# LTC6268-diff-iso.net
KiCad netlist of a schematic drawn in Altium Designer
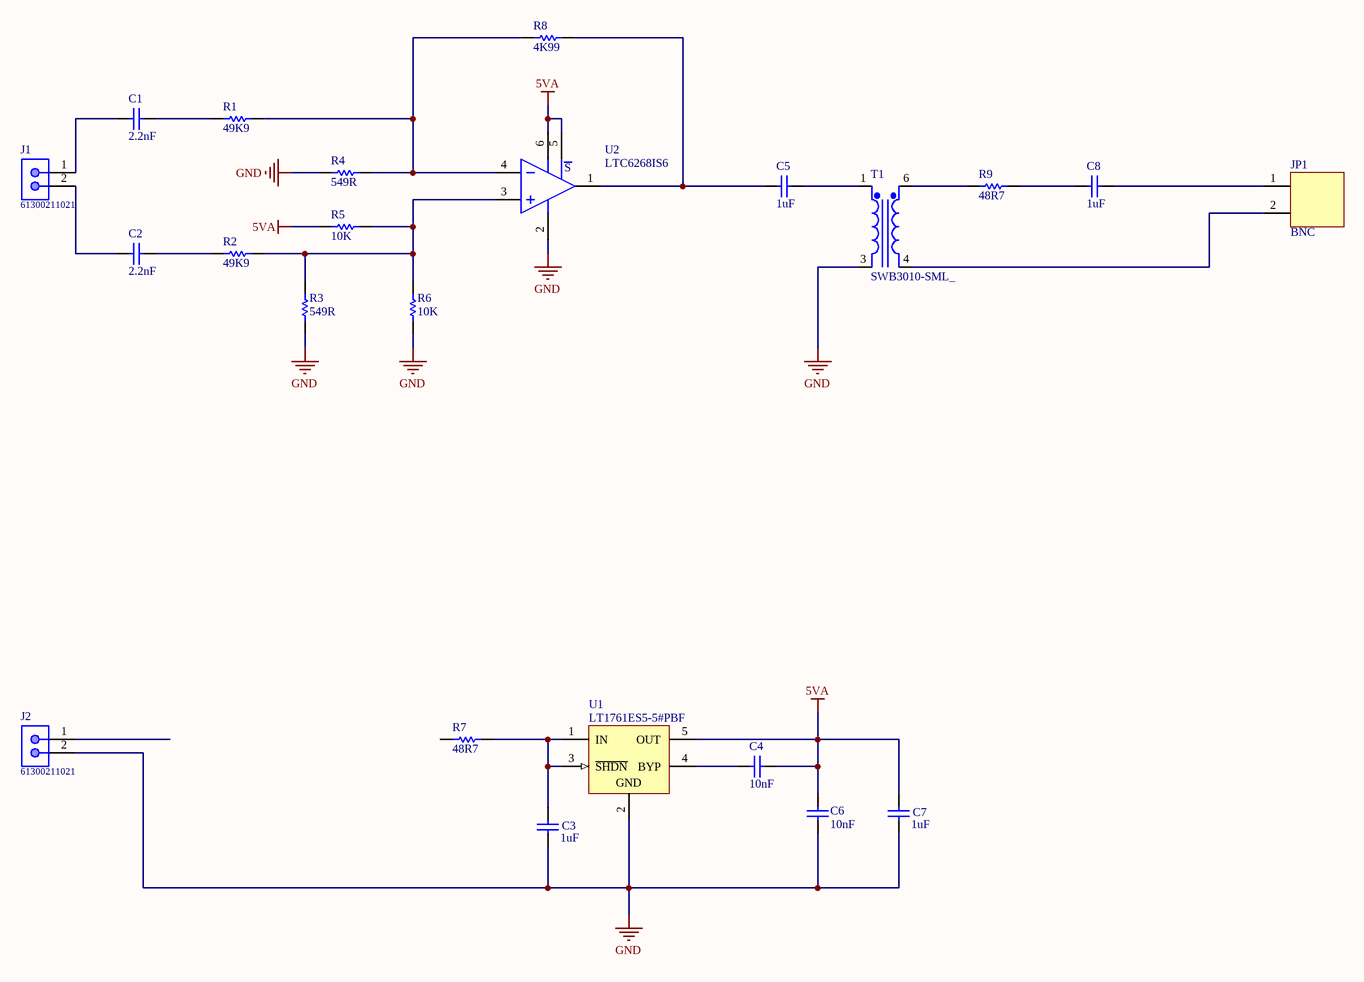
[diagram p0: LTC6268-diff-iso.SchDoc]

(export (version "E")
  (design (tool "Eeschema 10.0.6"))
  (components
    (comp (ref "C1")
      (value "2.2nF")
      (footprint "CAPC1210(3225)170_L")
      (description "CAP 2.2nF 630V ±5% 1210 (3225 Metric) Thickness 1.7mm SMD")
      (fields (field (name "TOLERANCE") "Â±5%") (field (name "MPN") "C1210C222JDGACTU"))
      (libsource (lib "Altium Content Vault") (part "CAP"))
    )
    (comp (ref "C2")
      (value "2.2nF")
      (footprint "CAPC1210(3225)170_L")
      (description "CAP 2.2nF 630V ±5% 1210 (3225 Metric) Thickness 1.7mm SMD")
      (fields (field (name "TOLERANCE") "Â±5%") (field (name "MPN") "C1210C222JDGACTU"))
      (libsource (lib "Altium Content Vault") (part "CAP"))
    )
    (comp (ref "C3")
      (value "1uF")
      (footprint "CAPC0805(2012)145_L")
      (description "CAP 1uF 16V ±10% 0805 (2012 Metric) Thickness 1.45mm SMD")
      (fields (field (name "TOLERANCE") "Â±10%") (field (name "Comment") "CAP 1uF 16V 0805(2012)"))
      (libsource (lib "Altium Content Vault") (part "CAP"))
    )
    (comp (ref "C4")
      (value "10nF")
      (footprint "CAPC0402(1005)33_N")
      (description "CAP 10nF 16V ±10% 0402 (1005 Metric) Thickness 0.33mm SMD")
      (fields (field (name "TOLERANCE") "Â±10%") (field (name "Comment") "CAP 10nF 16V 0402(1005)"))
      (libsource (lib "Altium Content Vault") (part "CAP"))
    )
    (comp (ref "C5")
      (value "1uF")
      (footprint "CAPC1210(3225)135_L")
      (description "CAP FILM 1UF 20% 16VDC 1210")
      (fields (field (name "MPN") "FCA1210C105M-G2") (field (name "VOLTAGE") "16V"))
      (libsource (lib "altium-import") (part "root_0_CAP_1210_1UF16V_FCA_"))
    )
    (comp (ref "C6")
      (value "10nF")
      (footprint "CAPC0402(1005)33_N")
      (description "CAP 10nF 16V ±10% 0402 (1005 Metric) Thickness 0.33mm SMD")
      (fields (field (name "TOLERANCE") "Â±10%") (field (name "Comment") "CAP 10nF 16V 0402(1005)"))
      (libsource (lib "Altium Content Vault") (part "CAP"))
    )
    (comp (ref "C7")
      (value "1uF")
      (footprint "CAPC0805(2012)145_L")
      (description "CAP 1uF 16V ±10% 0805 (2012 Metric) Thickness 1.45mm SMD")
      (fields (field (name "TOLERANCE") "Â±10%") (field (name "Comment") "CAP 1uF 16V 0805(2012)"))
      (libsource (lib "Altium Content Vault") (part "CAP"))
    )
    (comp (ref "C8")
      (value "1uF")
      (footprint "CAPC1210(3225)135_L")
      (description "CAP FILM 1UF 20% 16VDC 1210")
      (fields (field (name "MPN") "FCA1210C105M-G2") (field (name "VOLTAGE") "16V"))
      (libsource (lib "altium-import") (part "root_0_CAP_1210_1UF16V_FCA_"))
    )
    (comp (ref "J1")
      (value "61300211021")
      (footprint "61300211021")
      (description "THT Angled Pin Header WR-PHD, Pitch 2.54 mm, Single Row, 2 pins")
      (fields (field (name "PUBLISHER") "Wurth Elektronik"))
      (libsource (lib "altium-import") (part "root_0_mirrored_61300211021_"))
    )
    (comp (ref "J2")
      (value "61300211021")
      (footprint "61300211021")
      (description "THT Angled Pin Header WR-PHD, Pitch 2.54 mm, Single Row, 2 pins")
      (fields (field (name "PUBLISHER") "Wurth Elektronik"))
      (libsource (lib "altium-import") (part "root_0_mirrored_61300211021_"))
    )
    (comp (ref "JP1")
      (value "BNC")
      (footprint "CONN-BNC-1-1337542-0")
      (description "BNC Connector Jack, Female Socket 50 Ohm Panel Mount, Through Hole, Right Angle Solder")
      (fields (field (name "MPN") "1-1337542-0"))
      (libsource (lib "altium-import") (part "root_0_CONN-BNC-1-1337542-0_"))
    )
    (comp (ref "R1")
      (value "49K9")
      (footprint "RESC0402(1005)_N")
      (description "49K9 0.063W 1% 0402 (1005 Metric)  SMD")
      (fields (field (name "POWER") "0.063 W") (field (name "TOLERANCE") "1 %"))
      (libsource (lib "Altium Content Vault") (part "RES"))
    )
    (comp (ref "R2")
      (value "49K9")
      (footprint "RESC0402(1005)_N")
      (description "49K9 0.063W 1% 0402 (1005 Metric)  SMD")
      (fields (field (name "POWER") "0.063 W") (field (name "TOLERANCE") "1 %"))
      (libsource (lib "Altium Content Vault") (part "RES"))
    )
    (comp (ref "R3")
      (value "549R")
      (footprint "RESC0402(1005)_N")
      (description "549R 0.063W 1% 0402 (1005 Metric)  SMD")
      (fields (field (name "TOLERANCE") "1 %") (field (name "POWER") "0.063 W"))
      (libsource (lib "Altium Content Vault") (part "RES"))
    )
    (comp (ref "R4")
      (value "549R")
      (footprint "RESC0402(1005)_N")
      (description "549R 0.063W 1% 0402 (1005 Metric)  SMD")
      (fields (field (name "TOLERANCE") "1 %") (field (name "POWER") "0.063 W"))
      (libsource (lib "Altium Content Vault") (part "RES"))
    )
    (comp (ref "R5")
      (value "10K")
      (footprint "RESC0402(1005)_N")
      (description "10K 0.063W 1% 0402 (1005 Metric)  SMD")
      (fields (field (name "TOLERANCE") "1 %") (field (name "POWER") "0.063 W"))
      (libsource (lib "Altium Content Vault") (part "RES"))
    )
    (comp (ref "R6")
      (value "10K")
      (footprint "RESC0402(1005)_N")
      (description "10K 0.063W 1% 0402 (1005 Metric)  SMD")
      (fields (field (name "TOLERANCE") "1 %") (field (name "POWER") "0.063 W"))
      (libsource (lib "Altium Content Vault") (part "RES"))
    )
    (comp (ref "R7")
      (value "48R7")
      (footprint "RESC0402(1005)_N")
      (description "48R7 0.063W 1% 0402 (1005 Metric)  SMD")
      (fields (field (name "TOLERANCE") "1 %") (field (name "POWER") "0.063 W"))
      (libsource (lib "Altium Content Vault") (part "RES"))
    )
    (comp (ref "R8")
      (value "4K99")
      (footprint "RESC0402(1005)_N")
      (description "4K99 0.063W 1% 0402 (1005 Metric)  SMD")
      (fields (field (name "TOLERANCE") "1 %") (field (name "POWER") "0.063 W"))
      (libsource (lib "Altium Content Vault") (part "RES"))
    )
    (comp (ref "R9")
      (value "48R7")
      (footprint "RESC0402(1005)_N")
      (description "48R7 0.063W 1% 0402 (1005 Metric)  SMD")
      (fields (field (name "TOLERANCE") "1 %") (field (name "POWER") "0.063 W"))
      (libsource (lib "Altium Content Vault") (part "RES"))
    )
    (comp (ref "T1")
      (value "SWB3010-SML_")
      (footprint "Coilcraft-SWB")
      (description "Wideband RF Transformers – SWB")
      (libsource (lib "wemo") (part "TRANS-SWB3010-SML_"))
    )
    (comp (ref "U1")
      (value "LT1761ES5-5#PBF")
      (footprint "LT-S5-5-TSOT-23_M")
      (fields (field (name "MANUFACTURER") "Linear Technology"))
      (libsource (lib "Altium Content Vault") (part "LT-LTXXXXX-S5-5"))
    )
    (comp (ref "U2")
      (value "LTC6268IS6")
      (footprint "LT-S6-6-TSOT-23_L")
      (description "IC OPAMP 500MHZ SGL FET TSOT23-6")
      (fields (field (name "MPN") "LTC6268IS6#TRMPBF"))
      (libsource (lib "altium-import") (part "root_0_IC-LINEAR-LTC6268IS6#TRMPBF_"))
    )
  )
  (nets
    (net (code "1") (name "5VA") (class "Default")
      (node (ref "C4") (pin "1") (pinfunction "1_1") (pintype "passive"))
      (node (ref "C6") (pin "1") (pinfunction "1_1") (pintype "passive"))
      (node (ref "C7") (pin "2") (pinfunction "2_2") (pintype "passive"))
      (node (ref "R5") (pin "2") (pinfunction "2_2") (pintype "passive"))
      (node (ref "U1") (pin "5") (pinfunction "OUT_5") (pintype "power_in"))
      (node (ref "U2") (pin "5") (pinfunction "SHUTDOWNn_5") (pintype "passive"))
      (node (ref "U2") (pin "6") (pinfunction "V+_6") (pintype "power_in"))
    )
    (net (code "2") (name "GND") (class "Default")
      (node (ref "C3") (pin "1") (pinfunction "1_1") (pintype "passive"))
      (node (ref "C6") (pin "2") (pinfunction "2_2") (pintype "passive"))
      (node (ref "C7") (pin "1") (pinfunction "1_1") (pintype "passive"))
      (node (ref "J2") (pin "2") (pinfunction "2_2") (pintype "passive"))
      (node (ref "R3") (pin "1") (pinfunction "1_1") (pintype "passive"))
      (node (ref "R4") (pin "2") (pinfunction "2_2") (pintype "passive"))
      (node (ref "R6") (pin "1") (pinfunction "1_1") (pintype "passive"))
      (node (ref "T1") (pin "3") (pinfunction "3_3") (pintype "passive"))
      (node (ref "U1") (pin "2") (pinfunction "GND_2") (pintype "power_in"))
      (node (ref "U2") (pin "2") (pinfunction "V-_2") (pintype "power_in"))
    )
    (net (code "3") (name "Net-(C1-Pad1)") (class "Default")
      (node (ref "C1") (pin "1") (pinfunction "1_1") (pintype "passive"))
      (node (ref "J1") (pin "1") (pinfunction "1_1") (pintype "passive"))
    )
    (net (code "4") (name "Net-(C1-Pad2)") (class "Default")
      (node (ref "C1") (pin "2") (pinfunction "2_2") (pintype "passive"))
      (node (ref "R1") (pin "1") (pinfunction "1_1") (pintype "passive"))
    )
    (net (code "5") (name "Net-(C2-Pad1)") (class "Default")
      (node (ref "C2") (pin "1") (pinfunction "1_1") (pintype "passive"))
      (node (ref "J1") (pin "2") (pinfunction "2_2") (pintype "passive"))
    )
    (net (code "6") (name "Net-(C2-Pad2)") (class "Default")
      (node (ref "C2") (pin "2") (pinfunction "2_2") (pintype "passive"))
      (node (ref "R2") (pin "2") (pinfunction "2_2") (pintype "passive"))
    )
    (net (code "7") (name "Net-(C5-Pad2)") (class "Default")
      (node (ref "C5") (pin "2") (pinfunction "2_2") (pintype "passive"))
      (node (ref "T1") (pin "1") (pinfunction "1_1") (pintype "passive"))
    )
    (net (code "8") (name "Net-(C8-Pad1)") (class "Default")
      (node (ref "C8") (pin "1") (pinfunction "1_1") (pintype "passive"))
      (node (ref "R9") (pin "2") (pinfunction "2_2") (pintype "passive"))
    )
    (net (code "9") (name "Net-(C8-Pad2)") (class "Default")
      (node (ref "C8") (pin "2") (pinfunction "2_2") (pintype "passive"))
      (node (ref "JP1") (pin "1") (pinfunction "1_1") (pintype "passive"))
    )
    (net (code "10") (name "Net-(JP1-Pad2)") (class "Default")
      (node (ref "JP1") (pin "2") (pinfunction "2_2") (pintype "passive"))
      (node (ref "T1") (pin "4") (pinfunction "4_4") (pintype "passive"))
    )
    (net (code "11") (name "Net-(R9-Pad1)") (class "Default")
      (node (ref "R9") (pin "1") (pinfunction "1_1") (pintype "passive"))
      (node (ref "T1") (pin "6") (pinfunction "6_6") (pintype "passive"))
    )
    (net (code "12") (name "Net-(U1-BYP)") (class "Default")
      (node (ref "C4") (pin "2") (pinfunction "2_2") (pintype "passive"))
      (node (ref "U1") (pin "4") (pinfunction "BYP_4") (pintype "passive"))
    )
    (net (code "13") (name "Net-(U1-IN)") (class "Default")
      (node (ref "C3") (pin "2") (pinfunction "2_2") (pintype "passive"))
      (node (ref "R7") (pin "2") (pinfunction "2_2") (pintype "passive"))
      (node (ref "U1") (pin "1") (pinfunction "IN_1") (pintype "power_in"))
      (node (ref "U1") (pin "3") (pinfunction "~{SHDN}_3") (pintype "input"))
    )
    (net (code "14") (name "Net-(U2-IN1+)") (class "Default")
      (node (ref "R2") (pin "1") (pinfunction "1_1") (pintype "passive"))
      (node (ref "R3") (pin "2") (pinfunction "2_2") (pintype "passive"))
      (node (ref "R5") (pin "1") (pinfunction "1_1") (pintype "passive"))
      (node (ref "R6") (pin "2") (pinfunction "2_2") (pintype "passive"))
      (node (ref "U2") (pin "3") (pinfunction "IN1+_3") (pintype "passive"))
    )
    (net (code "15") (name "Net-(U2-IN1-)") (class "Default")
      (node (ref "R1") (pin "2") (pinfunction "2_2") (pintype "passive"))
      (node (ref "R4") (pin "1") (pinfunction "1_1") (pintype "passive"))
      (node (ref "R8") (pin "2") (pinfunction "2_2") (pintype "passive"))
      (node (ref "U2") (pin "4") (pinfunction "IN1-_4") (pintype "passive"))
    )
    (net (code "16") (name "Net-(U2-OUT1)") (class "Default")
      (node (ref "C5") (pin "1") (pinfunction "1_1") (pintype "passive"))
      (node (ref "R8") (pin "1") (pinfunction "1_1") (pintype "passive"))
      (node (ref "U2") (pin "1") (pinfunction "OUT1_1") (pintype "passive"))
    )
    (net (code "17") (name "unconnected-(J2-Pad1)") (class "Default")
      (node (ref "J2") (pin "1") (pinfunction "1_1") (pintype "passive"))
    )
    (net (code "18") (name "unconnected-(R7-Pad1)") (class "Default")
      (node (ref "R7") (pin "1") (pinfunction "1_1") (pintype "passive"))
    )
  )
)
